# RDA5807M.net
KiCad netlist of a schematic drawn in EAGLE
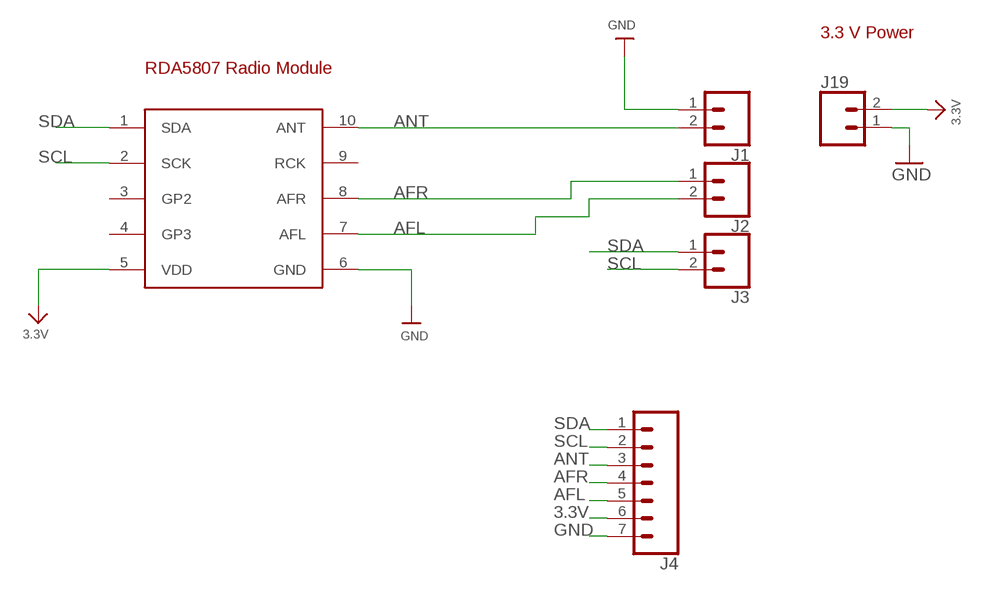
[diagram p0: schematic, sheet 1]

(export (version "E")
  (design (tool "Eeschema 10.0.6"))
  (components
    (comp (ref "J1")
      (value "CONN_025MM")
      (footprint "eagle-import:SCREWTERMINAL-5MM-2")
      (libsource (lib "eagle-import") (part "CONN_025MM"))
    )
    (comp (ref "J2")
      (value "CONN_025MM")
      (footprint "eagle-import:SCREWTERMINAL-5MM-2")
      (libsource (lib "eagle-import") (part "CONN_025MM"))
    )
    (comp (ref "J3")
      (value "CONN_025MM")
      (footprint "eagle-import:SCREWTERMINAL-5MM-2")
      (libsource (lib "eagle-import") (part "CONN_025MM"))
    )
    (comp (ref "J4")
      (value "CONN_07")
      (footprint "eagle-import:1X07")
      (libsource (lib "eagle-import") (part "CONN_07"))
    )
    (comp (ref "J19")
      (value "CONN_025MM")
      (footprint "eagle-import:SCREWTERMINAL-5MM-2")
      (libsource (lib "eagle-import") (part "CONN_025MM"))
    )
    (comp (ref "U$17")
      (value "RDA5807_RADIO")
      (footprint "eagle-import:RDA5807")
      (libsource (lib "eagle-import") (part "RDA5807_RADIO"))
    )
  )
  (nets
    (net (code "1") (name "/AFL") (class "Default")
      (node (ref "J2") (pin "2") (pinfunction "2_2") (pintype "passive"))
      (node (ref "J4") (pin "5") (pinfunction "5_5") (pintype "passive"))
      (node (ref "U$17") (pin "7") (pinfunction "AFL_7") (pintype "bidirectional"))
    )
    (net (code "2") (name "/AFR") (class "Default")
      (node (ref "J2") (pin "1") (pinfunction "1_1") (pintype "passive"))
      (node (ref "J4") (pin "4") (pinfunction "4_4") (pintype "passive"))
      (node (ref "U$17") (pin "8") (pinfunction "AFR_8") (pintype "bidirectional"))
    )
    (net (code "3") (name "/ANT") (class "Default")
      (node (ref "J1") (pin "2") (pinfunction "2_2") (pintype "passive"))
      (node (ref "J4") (pin "3") (pinfunction "3_3") (pintype "passive"))
      (node (ref "U$17") (pin "10") (pinfunction "ANT_10") (pintype "bidirectional"))
    )
    (net (code "4") (name "/SCL") (class "Default")
      (node (ref "J3") (pin "2") (pinfunction "2_2") (pintype "passive"))
      (node (ref "J4") (pin "2") (pinfunction "2_2") (pintype "passive"))
      (node (ref "U$17") (pin "2") (pinfunction "SCK_2") (pintype "bidirectional"))
    )
    (net (code "5") (name "/SDA") (class "Default")
      (node (ref "J3") (pin "1") (pinfunction "1_1") (pintype "passive"))
      (node (ref "J4") (pin "1") (pinfunction "1_1") (pintype "passive"))
      (node (ref "U$17") (pin "1") (pinfunction "SDA_1") (pintype "bidirectional"))
    )
    (net (code "6") (name "3.3V") (class "Default")
      (node (ref "J19") (pin "2") (pinfunction "2_2") (pintype "passive"))
      (node (ref "J4") (pin "6") (pinfunction "6_6") (pintype "passive"))
      (node (ref "U$17") (pin "5") (pinfunction "VDD_5") (pintype "bidirectional"))
    )
    (net (code "7") (name "GND") (class "Default")
      (node (ref "J1") (pin "1") (pinfunction "1_1") (pintype "passive"))
      (node (ref "J19") (pin "1") (pinfunction "1_1") (pintype "passive"))
      (node (ref "J4") (pin "7") (pinfunction "7_7") (pintype "passive"))
      (node (ref "U$17") (pin "6") (pinfunction "GND_6") (pintype "bidirectional"))
    )
    (net (code "8") (name "unconnected-(U$17-GP2-Pad3)") (class "Default")
      (node (ref "U$17") (pin "3") (pinfunction "GP2_3") (pintype "bidirectional"))
    )
    (net (code "9") (name "unconnected-(U$17-GP3-Pad4)") (class "Default")
      (node (ref "U$17") (pin "4") (pinfunction "GP3_4") (pintype "bidirectional"))
    )
    (net (code "10") (name "unconnected-(U$17-RCK-Pad9)") (class "Default")
      (node (ref "U$17") (pin "9") (pinfunction "RCK_9") (pintype "bidirectional"))
    )
  )
)
